# power.net
KiCad netlist of a schematic drawn in Altium Designer
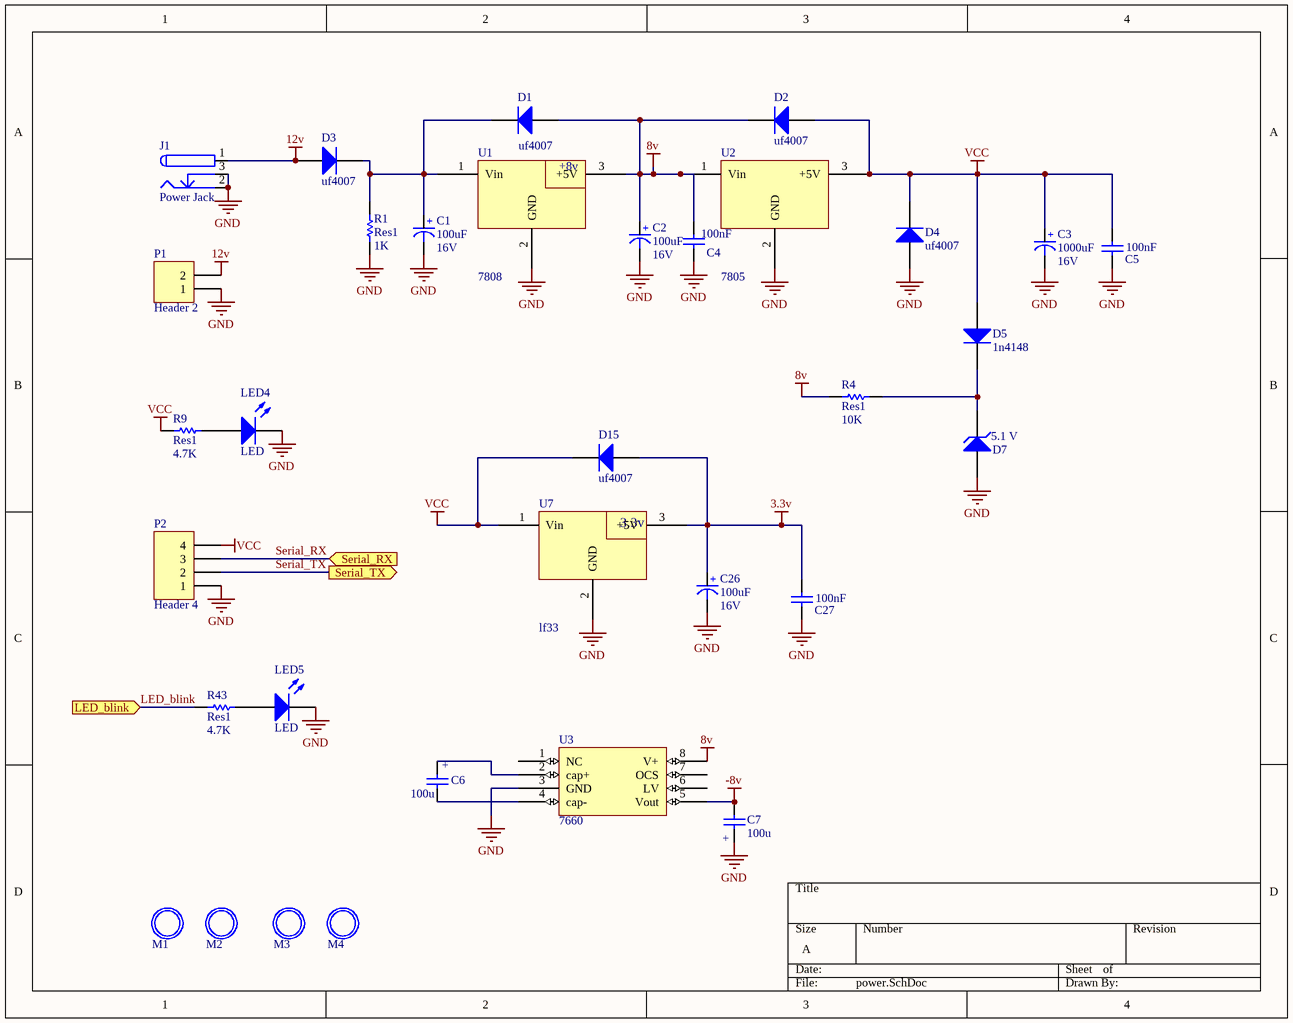
[diagram p0: power.SchDoc]

(export (version "E")
  (design (tool "Eeschema 10.0.6"))
  (components
    (comp (ref "C1")
      (value "100uF")
      (footprint "cap 01")
      (description "Polar Capacitor")
      (fields (field (name "VOLTAGE") "16V") (field (name "DESIGNER") "Saeid Jorablo"))
      (libsource (lib "My Library") (part "Cap-Polar"))
    )
    (comp (ref "C2")
      (value "100uF")
      (footprint "cap 01")
      (description "Polar Capacitor")
      (fields (field (name "VOLTAGE") "16V") (field (name "DESIGNER") "Saeid Jorablo"))
      (libsource (lib "My Library") (part "Cap-Polar"))
    )
    (comp (ref "C3")
      (value "1000uF")
      (footprint "cap 03")
      (description "Polar Capacitor")
      (fields (field (name "VOLTAGE") "16V") (field (name "DESIGNER") "Saeid Jorablo"))
      (libsource (lib "My Library") (part "Cap-Polar"))
    )
    (comp (ref "C4")
      (value "100nF")
      (footprint "CAP 1206 (3216X15L)")
      (description "CAP-100Nf")
      (fields (field (name "Comment") "Cap"))
      (libsource (lib "Altium library (www.AVRelec.com)") (part "Cap ceramic"))
    )
    (comp (ref "C5")
      (value "100nF")
      (footprint "CAP 1206 (3216X15L)")
      (description "CAP-100Nf")
      (fields (field (name "Comment") "Cap"))
      (libsource (lib "Altium library (www.AVRelec.com)") (part "Cap ceramic"))
    )
    (comp (ref "C6")
      (value "100u")
      (footprint "cap 01")
      (description "CAP-3300Uf")
      (fields (field (name "Comment") "Cap"))
      (libsource (lib "Altium library (www.AVRelec.com)") (part "Cap Pol"))
    )
    (comp (ref "C7")
      (value "100u")
      (footprint "cap 01")
      (description "CAP-3300Uf")
      (fields (field (name "Comment") "Cap"))
      (libsource (lib "Altium library (www.AVRelec.com)") (part "Cap Pol"))
    )
    (comp (ref "C26")
      (value "100uF")
      (footprint "cap 01")
      (description "Polar Capacitor")
      (fields (field (name "VOLTAGE") "16V") (field (name "DESIGNER") "Saeid Jorablo"))
      (libsource (lib "My Library") (part "Cap-Polar"))
    )
    (comp (ref "C27")
      (value "100nF")
      (footprint "CAP 1206 (3216X15L)")
      (description "CAP-100Nf")
      (fields (field (name "Comment") "Cap"))
      (libsource (lib "Altium library (www.AVRelec.com)") (part "Cap ceramic"))
    )
    (comp (ref "D1")
      (value "uf4007")
      (footprint "SMA DIODE 2")
      (description "1 Amp General Purpose Rectifier")
      (fields (field (name "PUBLISHER") "Altium Limited"))
      (libsource (lib "Miscellaneous Devices") (part "Diode 1N4007"))
    )
    (comp (ref "D2")
      (value "uf4007")
      (footprint "SMA DIODE 2")
      (description "1 Amp General Purpose Rectifier")
      (fields (field (name "PUBLISHER") "Altium Limited"))
      (libsource (lib "Miscellaneous Devices") (part "Diode 1N4007"))
    )
    (comp (ref "D3")
      (value "uf4007")
      (footprint "SMA DIODE 2")
      (description "1 Amp General Purpose Rectifier")
      (fields (field (name "PUBLISHER") "Altium Limited"))
      (libsource (lib "Miscellaneous Devices") (part "Diode 1N4007"))
    )
    (comp (ref "D4")
      (value "uf4007")
      (footprint "SMA DIODE 2")
      (description "1 Amp General Purpose Rectifier")
      (fields (field (name "PUBLISHER") "Altium Limited"))
      (libsource (lib "Miscellaneous Devices") (part "Diode 1N4007"))
    )
    (comp (ref "D5")
      (value "1n4148")
      (footprint "LL4148")
      (description "High Conductance Fast Diode")
      (fields (field (name "PUBLISHER") "Altium Limited"))
      (libsource (lib "Miscellaneous Devices") (part "Diode 1N4148"))
    )
    (comp (ref "D7")
      (value "Diode Zener")
      (footprint "LL4148")
      (description "Zener Diode")
      (fields (field (name "VOLTAGE") "5.1 V") (field (name "DESIGNER") "Saeid Jorablo"))
      (libsource (lib "My Library") (part "Diode Zener"))
    )
    (comp (ref "D15")
      (value "uf4007")
      (footprint "SMA DIODE 2")
      (description "1 Amp General Purpose Rectifier")
      (fields (field (name "PUBLISHER") "Altium Limited"))
      (libsource (lib "Miscellaneous Devices") (part "Diode 1N4007"))
    )
    (comp (ref "J1")
      (value "Power Jack")
      (footprint "Power Jack")
      (fields (field (name "DESIGNER") "Saeid Jorablo"))
      (libsource (lib "My Library") (part "Power Jack"))
    )
    (comp (ref "LED4")
      (value "LED")
      (footprint "LED 1206")
      (description "Typical INFRARED GaAs LED")
      (fields (field (name "PUBLISHER") "Altium Limited"))
      (libsource (lib "Altium library (www.AVRelec.com)") (part "LED"))
    )
    (comp (ref "LED5")
      (value "LED")
      (footprint "LED 1206")
      (description "Typical INFRARED GaAs LED")
      (fields (field (name "PUBLISHER") "Altium Limited"))
      (libsource (lib "Altium library (www.AVRelec.com)") (part "LED"))
    )
    (comp (ref "M1")
      (value "Screw")
      (footprint "Board Screw")
      (description "Board Screw With Spacer")
      (libsource (lib "Altium") (part "Board Screw"))
    )
    (comp (ref "M2")
      (value "Screw")
      (footprint "Board Screw")
      (description "Board Screw With Spacer")
      (libsource (lib "Altium") (part "Board Screw"))
    )
    (comp (ref "M3")
      (value "Screw")
      (footprint "Board Screw")
      (description "Board Screw With Spacer")
      (libsource (lib "Altium") (part "Board Screw"))
    )
    (comp (ref "M4")
      (value "Screw")
      (footprint "Board Screw")
      (description "Board Screw With Spacer")
      (libsource (lib "Altium") (part "Board Screw"))
    )
    (comp (ref "P1")
      (value "Header 2")
      (footprint "HDR1X2")
      (description "Header, 2-Pin")
      (fields (field (name "PUBLISHER") "Altium Limited"))
      (libsource (lib "Miscellaneous Connectors") (part "Header 2"))
    )
    (comp (ref "P2")
      (value "Header 4")
      (footprint "HDR1X4")
      (description "Header, 4-Pin")
      (fields (field (name "PUBLISHER") "Altium Limited"))
      (libsource (lib "Miscellaneous Connectors") (part "Header 4"))
    )
    (comp (ref "R1")
      (value "Res1")
      (footprint "RES 1206 (3216X08L)")
      (description "Resistor")
      (fields (field (name "ALTIUM_VALUE") "1K") (field (name "PUBLISHER") "Altium Limited"))
      (libsource (lib "Miscellaneous Devices") (part "Res1"))
    )
    (comp (ref "R4")
      (value "Res1")
      (footprint "RES 1206 (3216X08L)")
      (description "Resistor")
      (fields (field (name "ALTIUM_VALUE") "10K") (field (name "PUBLISHER") "Altium Limited"))
      (libsource (lib "Miscellaneous Devices") (part "Res1"))
    )
    (comp (ref "R9")
      (value "Res1")
      (footprint "RES 1206 (3216X08L)")
      (description "Resistor")
      (fields (field (name "ALTIUM_VALUE") "4.7K") (field (name "PUBLISHER") "Altium Limited"))
      (libsource (lib "Miscellaneous Devices") (part "Res1"))
    )
    (comp (ref "R43")
      (value "Res1")
      (footprint "RES 1206 (3216X08L)")
      (description "Resistor")
      (fields (field (name "ALTIUM_VALUE") "4.7K") (field (name "PUBLISHER") "Altium Limited"))
      (libsource (lib "Miscellaneous Devices") (part "Res1"))
    )
    (comp (ref "U1")
      (value "7808")
      (footprint "REG-7805-WALL")
      (description "Regulator")
      (libsource (lib "Altium library (www.AVRelec.com)") (part "7805"))
    )
    (comp (ref "U2")
      (value "7805")
      (footprint "REG-7805-WALL")
      (description "Regulator")
      (libsource (lib "Altium library (www.AVRelec.com)") (part "7805"))
    )
    (comp (ref "U3") (value "7660") (footprint "SOIC8-Narrow") (libsource (lib "Schlib1") (part "7660")))
    (comp (ref "U7")
      (value "lf33")
      (footprint "REG-7805-WALL")
      (description "Regulator")
      (libsource (lib "Altium library (www.AVRelec.com)") (part "7805"))
    )
  )
  (nets
    (net (code "1") (name "-8v") (class "Default")
      (node (ref "C7") (pin "-") (pinfunction "-_-") (pintype "passive"))
      (node (ref "U3") (pin "5") (pinfunction "Vout_5") (pintype "bidirectional"))
    )
    (net (code "2") (name "/LED_blink") (class "Default")
      (node (ref "R43") (pin "1") (pinfunction "1_1") (pintype "passive"))
    )
    (net (code "3") (name "/Serial_RX") (class "Default")
      (node (ref "P2") (pin "3") (pinfunction "3_3") (pintype "passive"))
    )
    (net (code "4") (name "/Serial_TX") (class "Default")
      (node (ref "P2") (pin "2") (pinfunction "2_2") (pintype "passive"))
    )
    (net (code "5") (name "3.3v") (class "Default")
      (node (ref "C26") (pin "1") (pinfunction "+_1") (pintype "passive"))
      (node (ref "C27") (pin "2") (pinfunction "2_2") (pintype "passive"))
      (node (ref "D15") (pin "1") (pinfunction "A_1") (pintype "passive"))
      (node (ref "U7") (pin "3") (pinfunction "+5V_3") (pintype "power_in"))
    )
    (net (code "6") (name "8v") (class "Default")
      (node (ref "C2") (pin "1") (pinfunction "+_1") (pintype "passive"))
      (node (ref "C4") (pin "2") (pinfunction "2_2") (pintype "passive"))
      (node (ref "D1") (pin "1") (pinfunction "A_1") (pintype "passive"))
      (node (ref "D2") (pin "2") (pinfunction "K_2") (pintype "passive"))
      (node (ref "R4") (pin "1") (pinfunction "1_1") (pintype "passive"))
      (node (ref "U1") (pin "3") (pinfunction "+5V_3") (pintype "power_in"))
      (node (ref "U2") (pin "1") (pinfunction "Vin_1") (pintype "power_in"))
      (node (ref "U3") (pin "8") (pinfunction "V+_8") (pintype "bidirectional"))
    )
    (net (code "7") (name "12v") (class "Default")
      (node (ref "D3") (pin "1") (pinfunction "A_1") (pintype "passive"))
      (node (ref "J1") (pin "1") (pinfunction "1_1") (pintype "power_in"))
      (node (ref "P1") (pin "2") (pinfunction "2_2") (pintype "passive"))
    )
    (net (code "8") (name "GND") (class "Default")
      (node (ref "C1") (pin "2") (pinfunction "-_2") (pintype "passive"))
      (node (ref "C2") (pin "2") (pinfunction "-_2") (pintype "passive"))
      (node (ref "C26") (pin "2") (pinfunction "-_2") (pintype "passive"))
      (node (ref "C27") (pin "1") (pinfunction "1_1") (pintype "passive"))
      (node (ref "C3") (pin "2") (pinfunction "-_2") (pintype "passive"))
      (node (ref "C4") (pin "1") (pinfunction "1_1") (pintype "passive"))
      (node (ref "C5") (pin "1") (pinfunction "1_1") (pintype "passive"))
      (node (ref "C7") (pin "+") (pinfunction "+_+") (pintype "passive"))
      (node (ref "D4") (pin "1") (pinfunction "A_1") (pintype "passive"))
      (node (ref "D7") (pin "1") (pinfunction "A_1") (pintype "passive"))
      (node (ref "J1") (pin "2") (pinfunction "2_2") (pintype "power_in"))
      (node (ref "J1") (pin "3") (pinfunction "3_3") (pintype "power_in"))
      (node (ref "LED4") (pin "K") (pinfunction "K_K") (pintype "passive"))
      (node (ref "LED5") (pin "K") (pinfunction "K_K") (pintype "passive"))
      (node (ref "P1") (pin "1") (pinfunction "1_1") (pintype "passive"))
      (node (ref "P2") (pin "1") (pinfunction "1_1") (pintype "passive"))
      (node (ref "R1") (pin "1") (pinfunction "1_1") (pintype "passive"))
      (node (ref "U1") (pin "2") (pinfunction "GND_2") (pintype "power_in"))
      (node (ref "U2") (pin "2") (pinfunction "GND_2") (pintype "power_in"))
      (node (ref "U3") (pin "3") (pinfunction "GND_3") (pintype "power_in"))
      (node (ref "U7") (pin "2") (pinfunction "GND_2") (pintype "power_in"))
    )
    (net (code "9") (name "Net-(C1-+)") (class "Default")
      (node (ref "C1") (pin "1") (pinfunction "+_1") (pintype "passive"))
      (node (ref "D1") (pin "2") (pinfunction "K_2") (pintype "passive"))
      (node (ref "D3") (pin "2") (pinfunction "K_2") (pintype "passive"))
      (node (ref "R1") (pin "2") (pinfunction "2_2") (pintype "passive"))
      (node (ref "U1") (pin "1") (pinfunction "Vin_1") (pintype "power_in"))
    )
    (net (code "10") (name "Net-(D5-K)") (class "Default")
      (node (ref "D5") (pin "2") (pinfunction "K_2") (pintype "passive"))
      (node (ref "D7") (pin "2") (pinfunction "K_2") (pintype "passive"))
      (node (ref "R4") (pin "2") (pinfunction "2_2") (pintype "passive"))
    )
    (net (code "11") (name "Net-(LED4-PadA)") (class "Default")
      (node (ref "LED4") (pin "A") (pinfunction "A_A") (pintype "passive"))
      (node (ref "R9") (pin "2") (pinfunction "2_2") (pintype "passive"))
    )
    (net (code "12") (name "Net-(LED5-PadA)") (class "Default")
      (node (ref "LED5") (pin "A") (pinfunction "A_A") (pintype "passive"))
      (node (ref "R43") (pin "2") (pinfunction "2_2") (pintype "passive"))
    )
    (net (code "13") (name "Net-(U3-cap+)") (class "Default")
      (node (ref "C6") (pin "+") (pinfunction "+_+") (pintype "passive"))
      (node (ref "U3") (pin "2") (pinfunction "cap+_2") (pintype "bidirectional"))
    )
    (net (code "14") (name "Net-(U3-cap-)") (class "Default")
      (node (ref "C6") (pin "-") (pinfunction "-_-") (pintype "passive"))
      (node (ref "U3") (pin "4") (pinfunction "cap-_4") (pintype "bidirectional"))
    )
    (net (code "15") (name "VCC") (class "Default")
      (node (ref "C3") (pin "1") (pinfunction "+_1") (pintype "passive"))
      (node (ref "C5") (pin "2") (pinfunction "2_2") (pintype "passive"))
      (node (ref "D15") (pin "2") (pinfunction "K_2") (pintype "passive"))
      (node (ref "D2") (pin "1") (pinfunction "A_1") (pintype "passive"))
      (node (ref "D4") (pin "2") (pinfunction "K_2") (pintype "passive"))
      (node (ref "D5") (pin "1") (pinfunction "A_1") (pintype "passive"))
      (node (ref "P2") (pin "4") (pinfunction "4_4") (pintype "passive"))
      (node (ref "R9") (pin "1") (pinfunction "1_1") (pintype "passive"))
      (node (ref "U2") (pin "3") (pinfunction "+5V_3") (pintype "power_in"))
      (node (ref "U7") (pin "1") (pinfunction "Vin_1") (pintype "power_in"))
    )
    (net (code "16") (name "unconnected-(U3-LV-Pad6)") (class "Default")
      (node (ref "U3") (pin "6") (pinfunction "LV_6") (pintype "bidirectional"))
    )
    (net (code "17") (name "unconnected-(U3-NC-Pad1)") (class "Default")
      (node (ref "U3") (pin "1") (pinfunction "NC_1") (pintype "bidirectional"))
    )
    (net (code "18") (name "unconnected-(U3-OCS-Pad7)") (class "Default")
      (node (ref "U3") (pin "7") (pinfunction "OCS_7") (pintype "bidirectional"))
    )
  )
)
